# Sheet1.net
KiCad netlist of a schematic drawn in Altium Designer
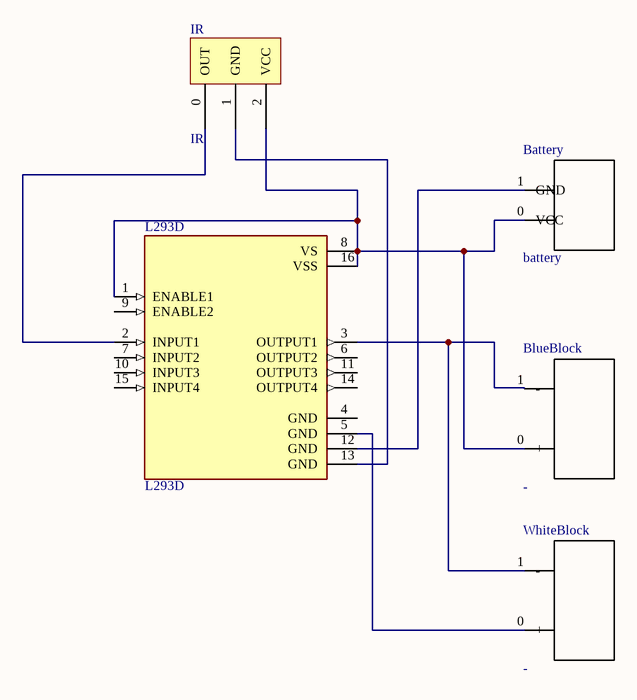
[diagram p0: Sheet1.SchDoc]

(export (version "E")
  (design (tool "Eeschema 10.0.6"))
  (components
    (comp (ref "Battery")
      (value "battery")
      (footprint "Battery")
      (libsource (lib "Schlib1") (part "battery"))
    )
    (comp (ref "BlueBlock") (value "-") (footprint "motor") (libsource (lib "Schlib1") (part "motor")))
    (comp (ref "IR") (value "IR") (footprint "IR") (libsource (lib "Schlib1") (part "IR")))
    (comp (ref "L293D")
      (value "L293D")
      (footprint "DIP880W50P254L2000H510Q16")
      (description "Bipolar Motor Driver - Parallel 16-PowerDIP")
      (fields (field (name "MF") "STMicroelectronics"))
      (libsource (lib "Schlib1") (part "L293D"))
    )
    (comp (ref "WhiteBlock") (value "-") (footprint "motor") (libsource (lib "Schlib1") (part "motor")))
  )
  (nets
    (net (code "1") (name "Net-(Battery-GND)") (class "Default")
      (node (ref "Battery") (pin "1") (pinfunction "GND_1") (pintype "passive"))
      (node (ref "L293D") (pin "12") (pinfunction "GND_12") (pintype "power_in"))
    )
    (net (code "2") (name "Net-(Battery-VCC)") (class "Default")
      (node (ref "Battery") (pin "0") (pinfunction "VCC_0") (pintype "passive"))
      (node (ref "BlueBlock") (pin "0") (pinfunction "+_0") (pintype "passive"))
      (node (ref "IR") (pin "2") (pinfunction "VCC_2") (pintype "passive"))
      (node (ref "L293D") (pin "1") (pinfunction "ENABLE1_1") (pintype "input"))
      (node (ref "L293D") (pin "16") (pinfunction "VSS_16") (pintype "power_in"))
      (node (ref "L293D") (pin "8") (pinfunction "VS_8") (pintype "power_in"))
    )
    (net (code "3") (name "Net-(BlueBlock--)") (class "Default")
      (node (ref "BlueBlock") (pin "1") (pinfunction "-_1") (pintype "passive"))
      (node (ref "L293D") (pin "3") (pinfunction "OUTPUT1_3") (pintype "output"))
      (node (ref "WhiteBlock") (pin "1") (pinfunction "-_1") (pintype "passive"))
    )
    (net (code "4") (name "Net-(IR-GND)") (class "Default")
      (node (ref "IR") (pin "1") (pinfunction "GND_1") (pintype "passive"))
      (node (ref "L293D") (pin "13") (pinfunction "GND_13") (pintype "power_in"))
    )
    (net (code "5") (name "Net-(IR-OUT)") (class "Default")
      (node (ref "IR") (pin "0") (pinfunction "OUT_0") (pintype "passive"))
      (node (ref "L293D") (pin "2") (pinfunction "INPUT1_2") (pintype "input"))
    )
    (net (code "6") (name "Net-(WhiteBlock-+)") (class "Default")
      (node (ref "L293D") (pin "5") (pinfunction "GND_5") (pintype "power_in"))
      (node (ref "WhiteBlock") (pin "0") (pinfunction "+_0") (pintype "passive"))
    )
    (net (code "7") (name "unconnected-(L293D-ENABLE2-Pad9)") (class "Default")
      (node (ref "L293D") (pin "9") (pinfunction "ENABLE2_9") (pintype "input"))
    )
    (net (code "8") (name "unconnected-(L293D-GND-Pad4)") (class "Default")
      (node (ref "L293D") (pin "4") (pinfunction "GND_4") (pintype "power_in"))
    )
    (net (code "9") (name "unconnected-(L293D-INPUT2-Pad7)") (class "Default")
      (node (ref "L293D") (pin "7") (pinfunction "INPUT2_7") (pintype "input"))
    )
    (net (code "10") (name "unconnected-(L293D-INPUT3-Pad10)") (class "Default")
      (node (ref "L293D") (pin "10") (pinfunction "INPUT3_10") (pintype "input"))
    )
    (net (code "11") (name "unconnected-(L293D-INPUT4-Pad15)") (class "Default")
      (node (ref "L293D") (pin "15") (pinfunction "INPUT4_15") (pintype "input"))
    )
    (net (code "12") (name "unconnected-(L293D-OUTPUT2-Pad6)") (class "Default")
      (node (ref "L293D") (pin "6") (pinfunction "OUTPUT2_6") (pintype "output"))
    )
    (net (code "13") (name "unconnected-(L293D-OUTPUT3-Pad11)") (class "Default")
      (node (ref "L293D") (pin "11") (pinfunction "OUTPUT3_11") (pintype "output"))
    )
    (net (code "14") (name "unconnected-(L293D-OUTPUT4-Pad14)") (class "Default")
      (node (ref "L293D") (pin "14") (pinfunction "OUTPUT4_14") (pintype "output"))
    )
  )
)
